# STM32Ethernet.net
KiCad netlist of a schematic drawn in Altium Designer
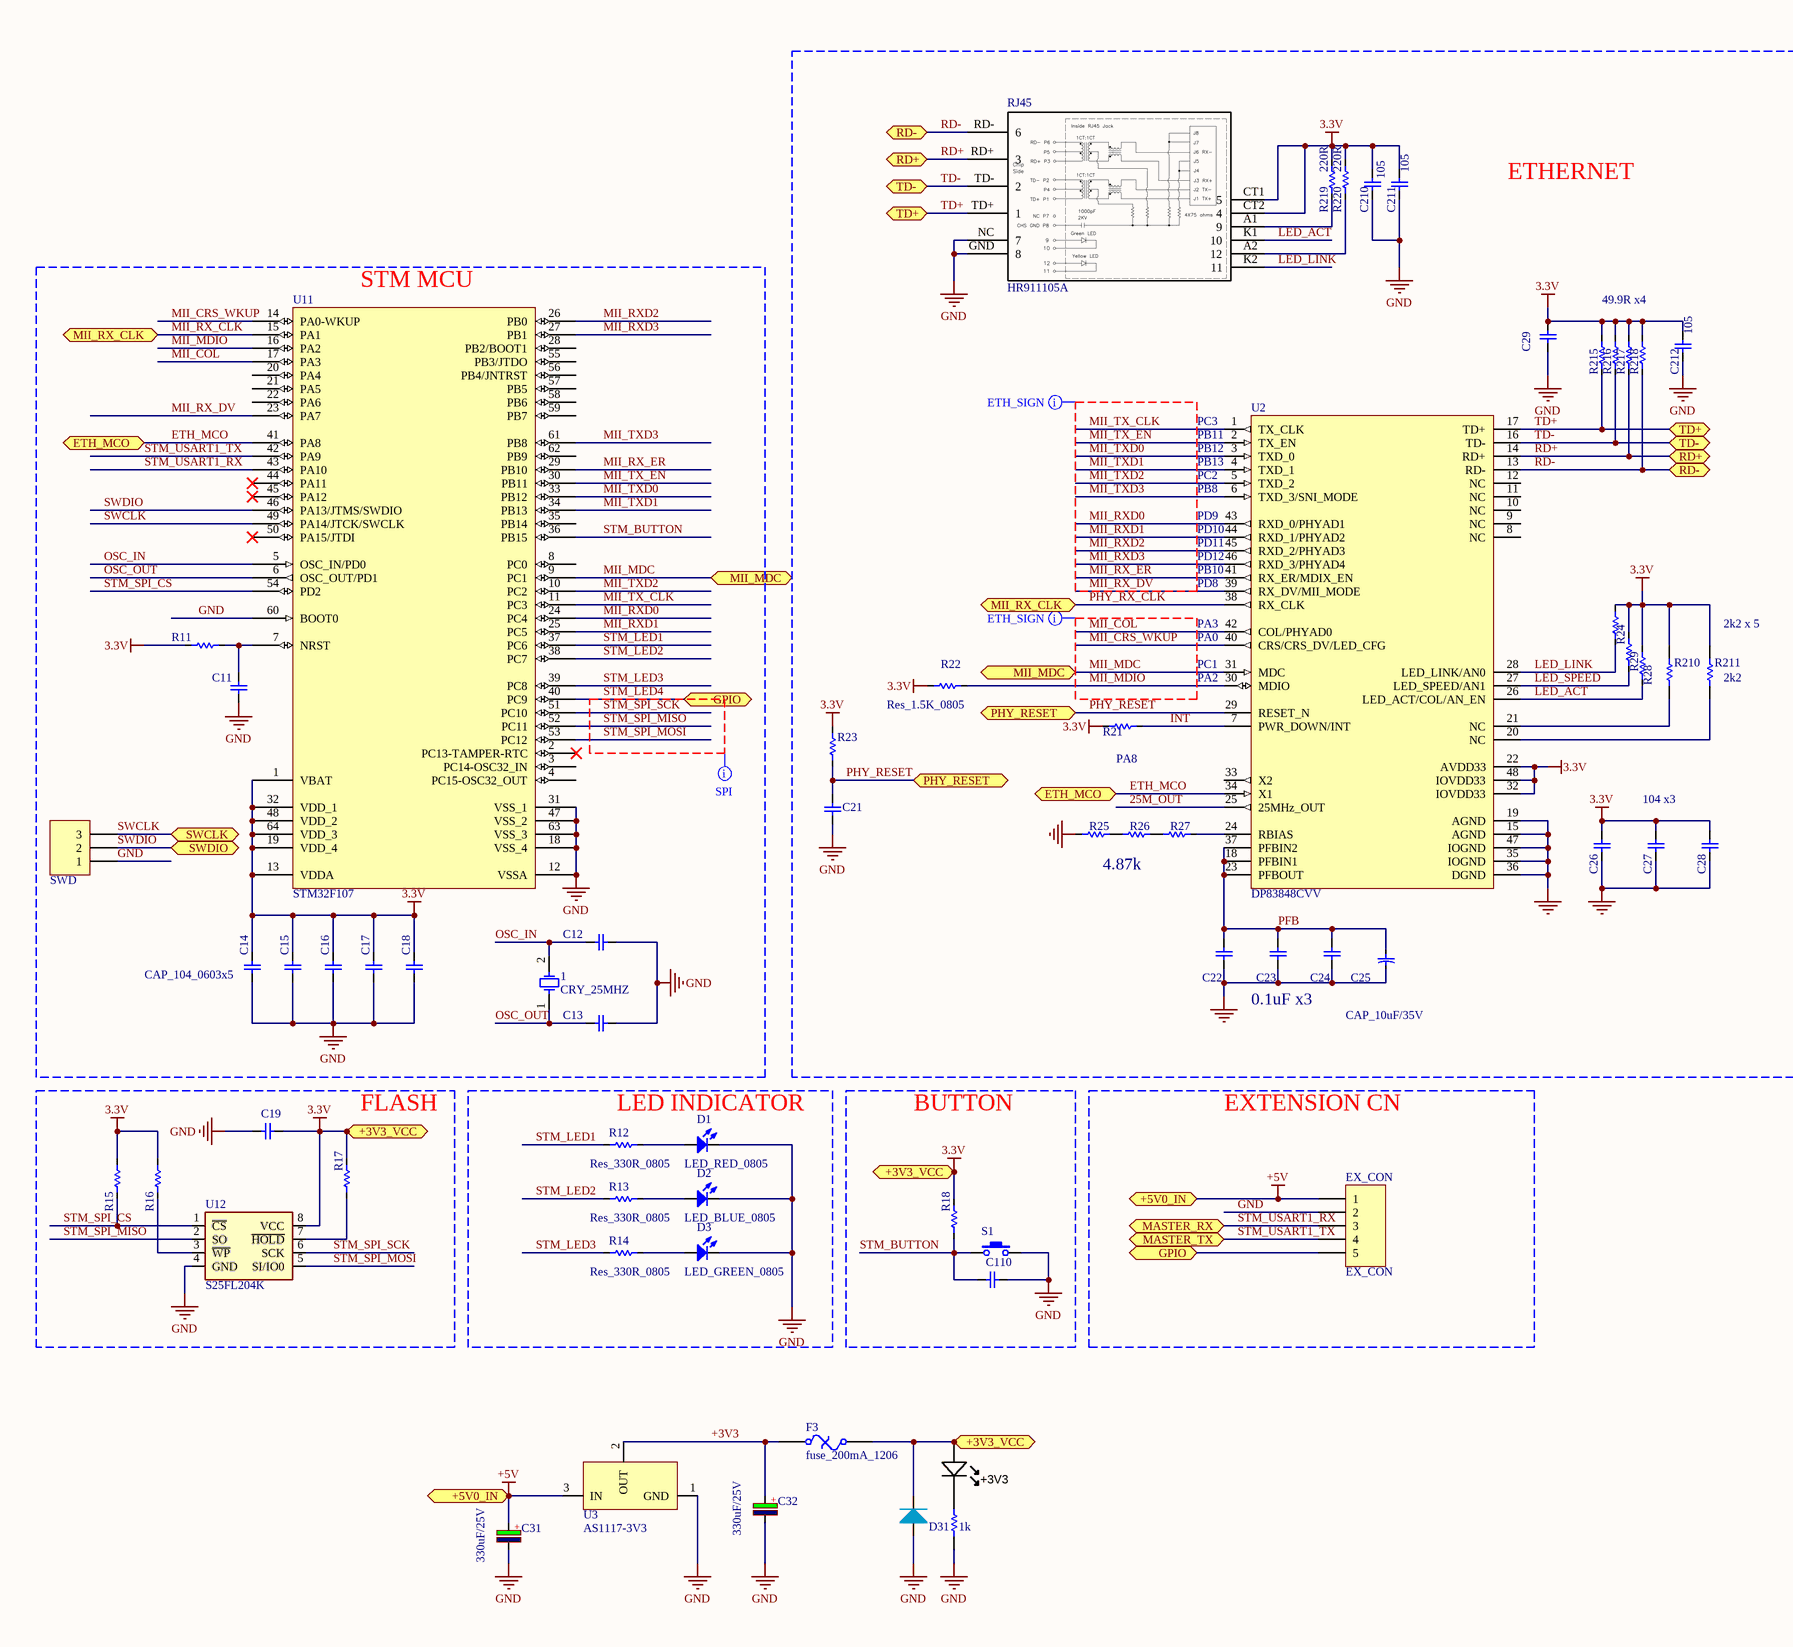
[diagram p0: STM32Ethernet.SchDoc, left]
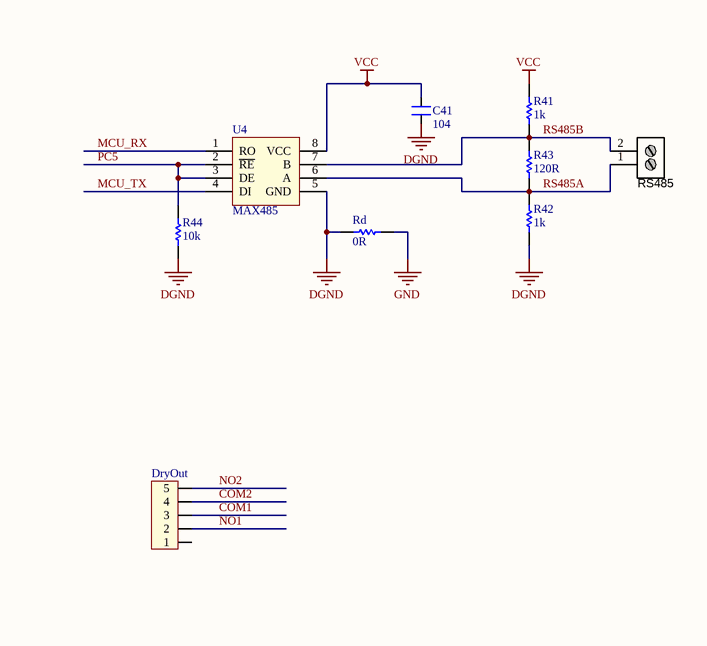
[diagram p1: STM32Ethernet.SchDoc, right]

(export (version "E")
  (design (tool "Eeschema 10.0.6"))
  (components
    (comp (ref "+3V3")
      (value "Blue")
      (footprint "LED-0805-K")
      (description "LED 0805 SMD Blue 100mcd 470nm")
      (libsource (lib "PBL - Light Sources") (part "LED_SMD_Blue_0805_100mcd"))
    )
    (comp (ref "1")
      (value "CRY_25MHZ")
      (footprint "cry")
      (description "Crystal Oscillator")
      (fields (field (name "PUBLISHER") "Altium Limited"))
      (libsource (lib "THU VIEN CHAN") (part "cry"))
    )
    (comp (ref "C11")
      (value "CAP_102_0603")
      (footprint "CAP_0805_TOP")
      (description "Capacitor")
      (fields (field (name "PUBLISHER") "Altium Limited"))
      (libsource (lib "THU VIEN CHAN") (part "Cap 1206 BUT"))
    )
    (comp (ref "C12")
      (value "CAP_18pF_0603")
      (footprint "CAP_0603_TOP")
      (description "Capacitor")
      (fields (field (name "PUBLISHER") "Altium Limited"))
      (libsource (lib "THU VIEN CHAN") (part "Cap 1206 BUT"))
    )
    (comp (ref "C13")
      (value "CAP_18pF_0603")
      (footprint "CAP_0603_TOP")
      (description "Capacitor")
      (fields (field (name "PUBLISHER") "Altium Limited"))
      (libsource (lib "THU VIEN CHAN") (part "Cap 1206 BUT"))
    )
    (comp (ref "C14")
      (value "CAP_104_0603")
      (footprint "CAPC1608N_F")
      (description "Capacitor")
      (fields (field (name "PUBLISHER") "Altium Limited"))
      (libsource (lib "THU VIEN CHAN") (part "Cap 1206 BUT"))
    )
    (comp (ref "C15")
      (value "CAP_104_0603")
      (footprint "CAPC1608N_F")
      (description "Capacitor")
      (fields (field (name "PUBLISHER") "Altium Limited"))
      (libsource (lib "THU VIEN CHAN") (part "Cap 1206 BUT"))
    )
    (comp (ref "C16")
      (value "CAP_104_0603")
      (footprint "CAPC1608N_F")
      (description "Capacitor")
      (fields (field (name "PUBLISHER") "Altium Limited"))
      (libsource (lib "THU VIEN CHAN") (part "Cap 1206 BUT"))
    )
    (comp (ref "C17")
      (value "CAP_104_0603")
      (footprint "CAPC1608N_F")
      (description "Capacitor")
      (fields (field (name "PUBLISHER") "Altium Limited"))
      (libsource (lib "THU VIEN CHAN") (part "Cap 1206 BUT"))
    )
    (comp (ref "C18")
      (value "CAP_104_0603")
      (footprint "CAPC1608N_F")
      (description "Capacitor")
      (fields (field (name "PUBLISHER") "Altium Limited"))
      (libsource (lib "THU VIEN CHAN") (part "Cap 1206 BUT"))
    )
    (comp (ref "C19")
      (value "CAP_104_0603")
      (footprint "CAP_0805_TOP")
      (description "Capacitor")
      (fields (field (name "PUBLISHER") "Altium Limited"))
      (libsource (lib "THU VIEN CHAN") (part "Cap 1206 BUT"))
    )
    (comp (ref "C21")
      (value "CAP_102_0603")
      (footprint "CAPC1608N_F")
      (description "Capacitor")
      (fields (field (name "PUBLISHER") "Altium Limited"))
      (libsource (lib "THU VIEN CHAN") (part "Cap 1206 BUT"))
    )
    (comp (ref "C22")
      (value "CAP_104_0603")
      (footprint "CAPC1608N_F")
      (description "Capacitor")
      (fields (field (name "PUBLISHER") "Altium Limited"))
      (libsource (lib "THU VIEN CHAN") (part "Cap 1206 BUT"))
    )
    (comp (ref "C23")
      (value "CAP_104_0603")
      (footprint "CAPC1608N_F")
      (description "Capacitor")
      (fields (field (name "PUBLISHER") "Altium Limited"))
      (libsource (lib "THU VIEN CHAN") (part "Cap 1206 BUT"))
    )
    (comp (ref "C24")
      (value "CAP_104_0603")
      (footprint "CAPC1608N_F")
      (description "Capacitor")
      (fields (field (name "PUBLISHER") "Altium Limited"))
      (libsource (lib "THU VIEN CHAN") (part "Cap 1206 BUT"))
    )
    (comp (ref "C25")
      (value "CAP_10uF/35V")
      (footprint "CAP_10uF/35V")
      (fields (field (name "PUBLISHER") "Altium Limited"))
      (libsource (lib "THU VIEN CHAN") (part "CAP P"))
    )
    (comp (ref "C26")
      (value "CAP_104_0603")
      (footprint "CAPC1608N_F")
      (description "Capacitor")
      (fields (field (name "PUBLISHER") "Altium Limited"))
      (libsource (lib "THU VIEN CHAN") (part "Cap 1206 BUT"))
    )
    (comp (ref "C27")
      (value "CAP_104_0603")
      (footprint "CAPC1608N_F")
      (description "Capacitor")
      (fields (field (name "PUBLISHER") "Altium Limited"))
      (libsource (lib "THU VIEN CHAN") (part "Cap 1206 BUT"))
    )
    (comp (ref "C28")
      (value "CAP_104_0603")
      (footprint "CAPC1608N_F")
      (description "Capacitor")
      (fields (field (name "PUBLISHER") "Altium Limited"))
      (libsource (lib "THU VIEN CHAN") (part "Cap 1206 BUT"))
    )
    (comp (ref "C29")
      (value "CAP_104_0603")
      (footprint "CAPC2012N_F")
      (description "Capacitor")
      (fields (field (name "PUBLISHER") "Altium Limited"))
      (libsource (lib "THU VIEN CHAN") (part "Cap 1206 BUT"))
    )
    (comp (ref "C31")
      (value "330uF/25V")
      (footprint "PBL - SMD Packages:CAPMP3528X210N")
      (description "Cap 1000uF/16V - 220uF/50V")
      (libsource (lib "heromap") (part "CP4"))
    )
    (comp (ref "C32")
      (value "330uF/25V")
      (footprint "CAPMP3528X210N")
      (description "Cap 1000uF/16V - 220uF/50V")
      (libsource (lib "heromap") (part "CP4"))
    )
    (comp (ref "C41")
      (value "104")
      (footprint "CAPC2012N_F")
      (fields (field (name "Comment") "100nF/104"))
      (libsource (lib "Tuan") (part "CAP NP"))
    )
    (comp (ref "C110")
      (value "CAP_102_0603")
      (footprint "CAP_0805_TOP")
      (description "Capacitor")
      (fields (field (name "PUBLISHER") "Altium Limited"))
      (libsource (lib "THU VIEN CHAN") (part "Cap 1206 BUT"))
    )
    (comp (ref "C210")
      (value "105")
      (footprint "CAPC1608N_F")
      (description "Capacitor")
      (fields (field (name "PUBLISHER") "Altium Limited"))
      (libsource (lib "THU VIEN CHAN") (part "Cap 1206 BUT"))
    )
    (comp (ref "C211")
      (value "105")
      (footprint "CAPC1608N_F")
      (description "Capacitor")
      (fields (field (name "PUBLISHER") "Altium Limited"))
      (libsource (lib "THU VIEN CHAN") (part "Cap 1206 BUT"))
    )
    (comp (ref "C212")
      (value "105")
      (footprint "CAPC2012N_F")
      (description "Capacitor")
      (fields (field (name "PUBLISHER") "Altium Limited"))
      (libsource (lib "THU VIEN CHAN") (part "Cap 1206 BUT"))
    )
    (comp (ref "D1")
      (value "LED_RED_0805")
      (footprint "LED 0805 TOP")
      (description "Typical INFRARED GaAs LED")
      (fields (field (name "PUBLISHER") "Altium Limited"))
      (libsource (lib "THU VIEN CHAN v1") (part "LED 0805 TOP"))
    )
    (comp (ref "D2")
      (value "LED_BLUE_0805")
      (footprint "LED 0805 TOP")
      (description "Typical INFRARED GaAs LED")
      (fields (field (name "PUBLISHER") "Altium Limited"))
      (libsource (lib "THU VIEN CHAN v1") (part "LED 0805 TOP"))
    )
    (comp (ref "D3")
      (value "LED_GREEN_0805")
      (footprint "LED 0805 TOP")
      (description "Typical INFRARED GaAs LED")
      (fields (field (name "PUBLISHER") "Altium Limited"))
      (libsource (lib "THU VIEN CHAN v1") (part "LED 0805 TOP"))
    )
    (comp (ref "D31") (value "Diode") (footprint "DO-214AC") (libsource (lib "Tuan") (part "Diode")))
    (comp (ref "DryOut")
      (value "JP5")
      (footprint "heromap:CON5")
      (description "Connector 5")
      (libsource (lib "heromap") (part "Con5"))
    )
    (comp (ref "EX_CON")
      (value "EX_CON")
      (footprint "HDR1X5")
      (description "Header, 5-Pin")
      (fields (field (name "PUBLISHER") "Altium Limited"))
      (libsource (lib "Miscellaneous Connectors") (part "Header 5"))
    )
    (comp (ref "F3")
      (value "fuse_200mA_1206")
      (footprint "SMD 1206")
      (description "Thermal Fuse")
      (fields (field (name "PUBLISHER") "Altium Limited"))
      (libsource (lib "Miscellaneous Devices") (part "Fuse Thermal"))
    )
    (comp (ref "R11")
      (value "Res_4.7K_0805")
      (footprint "RES_0805_TOP")
      (description "Resistor")
      (fields (field (name "PUBLISHER") "Altium Limited"))
      (libsource (lib "THU VIEN CHAN") (part "Res"))
    )
    (comp (ref "R12")
      (value "Res_330R_0805")
      (footprint "RES_0805_TOP")
      (description "Resistor")
      (fields (field (name "PUBLISHER") "Altium Limited"))
      (libsource (lib "THU VIEN CHAN") (part "Res"))
    )
    (comp (ref "R13")
      (value "Res_330R_0805")
      (footprint "RES_0805_TOP")
      (description "Resistor")
      (fields (field (name "PUBLISHER") "Altium Limited"))
      (libsource (lib "THU VIEN CHAN") (part "Res"))
    )
    (comp (ref "R14")
      (value "Res_330R_0805")
      (footprint "RES_0805_TOP")
      (description "Resistor")
      (fields (field (name "PUBLISHER") "Altium Limited"))
      (libsource (lib "THU VIEN CHAN") (part "Res"))
    )
    (comp (ref "R15")
      (value "Res_4.7K_0805")
      (footprint "RES_0805_TOP")
      (description "Resistor")
      (fields (field (name "PUBLISHER") "Altium Limited"))
      (libsource (lib "THU VIEN CHAN") (part "Res"))
    )
    (comp (ref "R16")
      (value "Res_4.7K_0805")
      (footprint "RES_0805_TOP")
      (description "Resistor")
      (fields (field (name "PUBLISHER") "Altium Limited"))
      (libsource (lib "THU VIEN CHAN") (part "Res"))
    )
    (comp (ref "R17")
      (value "Res_4.7K_0805")
      (footprint "RES_0805_TOP")
      (description "Resistor")
      (fields (field (name "PUBLISHER") "Altium Limited"))
      (libsource (lib "THU VIEN CHAN") (part "Res"))
    )
    (comp (ref "R18")
      (value "Res_4.7K_0805")
      (footprint "RES_0805_TOP")
      (description "Resistor")
      (fields (field (name "PUBLISHER") "Altium Limited"))
      (libsource (lib "THU VIEN CHAN") (part "Res"))
    )
    (comp (ref "R21")
      (value "Res_2.2K_0805")
      (footprint "RESC1608N_F")
      (description "Resistor")
      (fields (field (name "PUBLISHER") "Altium Limited"))
      (libsource (lib "THU VIEN CHAN") (part "Res"))
    )
    (comp (ref "R22")
      (value "Res_1.5K_0805")
      (footprint "RESC1608N_F")
      (description "Resistor")
      (fields (field (name "PUBLISHER") "Altium Limited"))
      (libsource (lib "") (part "Res_1"))
    )
    (comp (ref "R23")
      (value "Res_4.7K_0805")
      (footprint "RESC1608N_F")
      (description "Resistor")
      (fields (field (name "PUBLISHER") "Altium Limited"))
      (libsource (lib "") (part "Res_1"))
    )
    (comp (ref "R24")
      (value "Res_2.2K_0805")
      (footprint "RESC1608N_F")
      (description "Resistor")
      (fields (field (name "PUBLISHER") "Altium Limited"))
      (libsource (lib "THU VIEN CHAN") (part "Res"))
    )
    (comp (ref "R25")
      (value "Res_47R_0805")
      (footprint "RES_0805_TOP")
      (description "Resistor")
      (fields (field (name "PUBLISHER") "Altium Limited"))
      (libsource (lib "THU VIEN CHAN") (part "Res"))
    )
    (comp (ref "R26")
      (value "Res_120R_0805")
      (footprint "RES_0805_TOP")
      (description "Resistor")
      (fields (field (name "PUBLISHER") "Altium Limited"))
      (libsource (lib "THU VIEN CHAN") (part "Res"))
    )
    (comp (ref "R27")
      (value "Res_4.7K_0805")
      (footprint "RES_0805_TOP")
      (description "Resistor")
      (fields (field (name "PUBLISHER") "Altium Limited"))
      (libsource (lib "THU VIEN CHAN") (part "Res"))
    )
    (comp (ref "R28")
      (value "Res_0R_0603")
      (footprint "RESC1608N_F")
      (description "Resistor")
      (fields (field (name "PUBLISHER") "Altium Limited"))
      (libsource (lib "THU VIEN CHAN") (part "Res"))
    )
    (comp (ref "R29")
      (value "Res_0R_0603")
      (footprint "RESC1608N_F")
      (description "Resistor")
      (fields (field (name "PUBLISHER") "Altium Limited"))
      (libsource (lib "THU VIEN CHAN") (part "Res"))
    )
    (comp (ref "R41")
      (value "1k")
      (footprint "RESC2012N_F")
      (description "Tro dan")
      (libsource (lib "GPS_Clock_v12") (part "Res"))
    )
    (comp (ref "R42")
      (value "1k")
      (footprint "RESC2012N_F")
      (description "Tro dan")
      (libsource (lib "GPS_Clock_v12") (part "Res"))
    )
    (comp (ref "R43")
      (value "120R")
      (footprint "RESC2012N_F")
      (description "Tro dan")
      (fields (field (name "Comment") "330R"))
      (libsource (lib "GPS_Clock_v12") (part "Res"))
    )
    (comp (ref "R44")
      (value "10k")
      (footprint "RESC2012N_F")
      (description "Tro dan")
      (fields (field (name "Comment") "330R"))
      (libsource (lib "GPS_Clock_v12") (part "Res"))
    )
    (comp (ref "R210") (value "2k2") (footprint "RESC1608N_F") (libsource (lib "Tuan") (part "Res")))
    (comp (ref "R211") (value "2k2") (footprint "RESC1608N_F") (libsource (lib "Tuan") (part "Res")))
    (comp (ref "R215")
      (value "Res_49.9R_0805")
      (footprint "RES_0805_TOP")
      (description "Resistor")
      (fields (field (name "PUBLISHER") "Altium Limited"))
      (libsource (lib "THU VIEN CHAN") (part "Res"))
    )
    (comp (ref "R216")
      (value "Res_49.9R_0805")
      (footprint "RES_0805_TOP")
      (description "Resistor")
      (fields (field (name "PUBLISHER") "Altium Limited"))
      (libsource (lib "THU VIEN CHAN") (part "Res"))
    )
    (comp (ref "R217")
      (value "Res_49.9R_0805")
      (footprint "RES_0805_TOP")
      (description "Resistor")
      (fields (field (name "PUBLISHER") "Altium Limited"))
      (libsource (lib "THU VIEN CHAN") (part "Res"))
    )
    (comp (ref "R218")
      (value "Res_49.9R_0805")
      (footprint "RES_0805_TOP")
      (description "Resistor")
      (fields (field (name "PUBLISHER") "Altium Limited"))
      (libsource (lib "THU VIEN CHAN") (part "Res"))
    )
    (comp (ref "R219")
      (value "220R")
      (footprint "RESC1608N_F")
      (description "Resistor")
      (fields (field (name "PUBLISHER") "Altium Limited"))
      (libsource (lib "THU VIEN CHAN") (part "Res"))
    )
    (comp (ref "R220")
      (value "220R")
      (footprint "RESC1608N_F")
      (description "Resistor")
      (fields (field (name "PUBLISHER") "Altium Limited"))
      (libsource (lib "THU VIEN CHAN") (part "Res"))
    )
    (comp (ref "Rd")
      (value "0R")
      (footprint "RESC2012N_F")
      (fields (field (name "Comment") "Res"))
      (libsource (lib "Tuan") (part "Res"))
    )
    (comp (ref "RJ45") (value "HR911105A") (footprint "HR911105A") (libsource (lib "Tuan") (part "RJ45-LED")))
    (comp (ref "Rled")
      (value "1k")
      (footprint "RESC2012N_F")
      (fields (field (name "Comment") "Res_0805_1k"))
      (libsource (lib "Tuan") (part "Res"))
    )
    (comp (ref "RS485")
      (value "Stackable ScrewTerm")
      (footprint "2P_PCB1")
      (description "Terminal Block Screw Type THT 2-Position 3.81mm pitch")
      (libsource (lib "PBL - Connectors") (part "2P_ScrewTerm_90S_3.81MM"))
    )
    (comp (ref "S1")
      (value "BUTTON 2P")
      (footprint "Nut nhan 2 chan  dung")
      (description "Switch")
      (fields (field (name "PUBLISHER") "Altium Limited"))
      (libsource (lib "THU VIEN CHAN v1") (part "BUTTON 2P"))
    )
    (comp (ref "SWD")
      (value "Header 3")
      (footprint "heromap:HDR1X3")
      (description "Header, 3-Pin")
      (fields (field (name "PUBLISHER") "Altium Limited"))
      (libsource (lib "heromap") (part "Header 3"))
    )
    (comp (ref "U2")
      (value "DP83848CVV")
      (footprint "LQFP48")
      (libsource (lib "THU VIEN CHAN v1") (part "DP83848CVV"))
    )
    (comp (ref "U3") (value "AS1117-3V3") (footprint "SOT223-4N") (libsource (lib "Tuan") (part "AS1117")))
    (comp (ref "U4")
      (value "MAX485")
      (footprint "SO-8")
      (description "RS232 - RS485 (Same sn75176)")
      (libsource (lib "heromap") (part "MAX485"))
    )
    (comp (ref "U11")
      (value "STM32F107")
      (footprint "LQFP64_N")
      (description "STM32 ARM-based 32-bit MCU with 128 Kbytes Flash, 64-pin LQFP, Industrial Temperature")
      (fields (field (name "PUBLISHER") "Altium Limited"))
      (libsource (lib "ST Microcontroller 32-Bit STM32") (part "STM32F103RBT6"))
    )
    (comp (ref "U12")
      (value "S25FL204K")
      (footprint "SOIC_8")
      (libsource (lib "THU VIEN CHAN v1") (part "S25FL204K"))
    )
  )
  (nets
    (net (code "1") (name "+5V") (class "Default")
      (node (ref "C31") (pin "1") (pinfunction "1_1") (pintype "passive"))
      (node (ref "EX_CON") (pin "1") (pinfunction "1_1") (pintype "passive"))
      (node (ref "U3") (pin "3") (pinfunction "IN_3") (pintype "power_in"))
    )
    (net (code "2") (name "/+3V3") (class "Default")
      (node (ref "C32") (pin "1") (pinfunction "1_1") (pintype "passive"))
      (node (ref "F3") (pin "1") (pinfunction "1_1") (pintype "passive"))
      (node (ref "U3") (pin "2") (pinfunction "OUT_2") (pintype "power_in"))
    )
    (net (code "3") (name "/25M_OUT") (class "Default")
      (node (ref "U2") (pin "25") (pinfunction "25MHz_OUT_25") (pintype "output"))
    )
    (net (code "4") (name "/COM1") (class "Default")
      (node (ref "DryOut") (pin "3") (pinfunction "3_3") (pintype "passive"))
    )
    (net (code "5") (name "/COM2") (class "Default")
      (node (ref "DryOut") (pin "4") (pinfunction "4_4") (pintype "passive"))
    )
    (net (code "6") (name "/ETH_MCO") (class "Default")
      (node (ref "U11") (pin "41") (pinfunction "PA8_41") (pintype "bidirectional"))
      (node (ref "U2") (pin "34") (pinfunction "X1_34") (pintype "input"))
    )
    (net (code "7") (name "/INT") (class "Default")
      (node (ref "R21") (pin "1") (pinfunction "1_1") (pintype "passive"))
      (node (ref "U2") (pin "7") (pinfunction "PWR_DOWN/INT_7") (pintype "passive"))
    )
    (net (code "8") (name "/LED_ACT") (class "Default")
      (node (ref "R28") (pin "2") (pinfunction "2_2") (pintype "passive"))
      (node (ref "RJ45") (pin "K1") (pinfunction "10_K1") (pintype "passive"))
      (node (ref "U2") (pin "26") (pinfunction "LED_ACT/COL/AN_EN_26") (pintype "passive"))
    )
    (net (code "9") (name "/LED_LINK") (class "Default")
      (node (ref "R24") (pin "1") (pinfunction "1_1") (pintype "passive"))
      (node (ref "RJ45") (pin "K2") (pinfunction "11_K2") (pintype "passive"))
      (node (ref "U2") (pin "28") (pinfunction "LED_LINK/AN0_28") (pintype "passive"))
    )
    (net (code "10") (name "/LED_SPEED") (class "Default")
      (node (ref "R29") (pin "1") (pinfunction "1_1") (pintype "passive"))
      (node (ref "U2") (pin "27") (pinfunction "LED_SPEED/AN1_27") (pintype "passive"))
    )
    (net (code "11") (name "/MCU_RX") (class "Default")
      (node (ref "U4") (pin "1") (pinfunction "RO_1") (pintype "passive"))
    )
    (net (code "12") (name "/MCU_TX") (class "Default")
      (node (ref "U4") (pin "4") (pinfunction "DI_4") (pintype "passive"))
    )
    (net (code "13") (name "/MII_COL") (class "Default")
      (node (ref "U11") (pin "17") (pinfunction "PA3_17") (pintype "bidirectional"))
      (node (ref "U2") (pin "42") (pinfunction "COL/PHYAD0_42") (pintype "output"))
    )
    (net (code "14") (name "/MII_CRS_WKUP") (class "Default")
      (node (ref "U11") (pin "14") (pinfunction "PA0-WKUP_14") (pintype "bidirectional"))
      (node (ref "U2") (pin "40") (pinfunction "CRS/CRS_DV/LED_CFG_40") (pintype "output"))
    )
    (net (code "15") (name "/MII_MDC") (class "Default")
      (node (ref "U11") (pin "9") (pinfunction "PC1_9") (pintype "bidirectional"))
      (node (ref "U2") (pin "31") (pinfunction "MDC_31") (pintype "input"))
    )
    (net (code "16") (name "/MII_MDIO") (class "Default")
      (node (ref "R22") (pin "2") (pinfunction "2_2") (pintype "passive"))
      (node (ref "U11") (pin "16") (pinfunction "PA2_16") (pintype "bidirectional"))
      (node (ref "U2") (pin "30") (pinfunction "MDIO_30") (pintype "bidirectional"))
    )
    (net (code "17") (name "/MII_RXD0") (class "Default")
      (node (ref "U11") (pin "24") (pinfunction "PC4_24") (pintype "bidirectional"))
      (node (ref "U2") (pin "43") (pinfunction "RXD_0/PHYAD1_43") (pintype "output"))
    )
    (net (code "18") (name "/MII_RXD1") (class "Default")
      (node (ref "U11") (pin "25") (pinfunction "PC5_25") (pintype "bidirectional"))
      (node (ref "U2") (pin "44") (pinfunction "RXD_1/PHYAD2_44") (pintype "output"))
    )
    (net (code "19") (name "/MII_RXD2") (class "Default")
      (node (ref "U11") (pin "26") (pinfunction "PB0_26") (pintype "bidirectional"))
      (node (ref "U2") (pin "45") (pinfunction "RXD_2/PHYAD3_45") (pintype "output"))
    )
    (net (code "20") (name "/MII_RXD3") (class "Default")
      (node (ref "U11") (pin "27") (pinfunction "PB1_27") (pintype "bidirectional"))
      (node (ref "U2") (pin "46") (pinfunction "RXD_3/PHYAD4_46") (pintype "output"))
    )
    (net (code "21") (name "/MII_RX_CLK") (class "Default")
      (node (ref "U11") (pin "15") (pinfunction "PA1_15") (pintype "bidirectional"))
      (node (ref "U2") (pin "38") (pinfunction "RX_CLK_38") (pintype "output"))
    )
    (net (code "22") (name "/MII_RX_DV") (class "Default")
      (node (ref "U11") (pin "23") (pinfunction "PA7_23") (pintype "bidirectional"))
      (node (ref "U2") (pin "39") (pinfunction "RX_DV/MII_MODE_39") (pintype "output"))
    )
    (net (code "23") (name "/MII_RX_ER") (class "Default")
      (node (ref "U11") (pin "29") (pinfunction "PB10_29") (pintype "bidirectional"))
      (node (ref "U2") (pin "41") (pinfunction "RX_ER/MDIX_EN_41") (pintype "output"))
    )
    (net (code "24") (name "/MII_TXD0") (class "Default")
      (node (ref "U11") (pin "33") (pinfunction "PB12_33") (pintype "bidirectional"))
      (node (ref "U2") (pin "3") (pinfunction "TXD_0_3") (pintype "input"))
    )
    (net (code "25") (name "/MII_TXD1") (class "Default")
      (node (ref "U11") (pin "34") (pinfunction "PB13_34") (pintype "bidirectional"))
      (node (ref "U2") (pin "4") (pinfunction "TXD_1_4") (pintype "input"))
    )
    (net (code "26") (name "/MII_TXD2") (class "Default")
      (node (ref "U11") (pin "10") (pinfunction "PC2_10") (pintype "bidirectional"))
      (node (ref "U2") (pin "5") (pinfunction "TXD_2_5") (pintype "input"))
    )
    (net (code "27") (name "/MII_TXD3") (class "Default")
      (node (ref "U11") (pin "61") (pinfunction "PB8_61") (pintype "bidirectional"))
      (node (ref "U2") (pin "6") (pinfunction "TXD_3/SNI_MODE_6") (pintype "input"))
    )
    (net (code "28") (name "/MII_TX_CLK") (class "Default")
      (node (ref "U11") (pin "11") (pinfunction "PC3_11") (pintype "bidirectional"))
      (node (ref "U2") (pin "1") (pinfunction "TX_CLK_1") (pintype "output"))
    )
    (net (code "29") (name "/MII_TX_EN") (class "Default")
      (node (ref "U11") (pin "30") (pinfunction "PB11_30") (pintype "bidirectional"))
      (node (ref "U2") (pin "2") (pinfunction "TX_EN_2") (pintype "input"))
    )
    (net (code "30") (name "/NO1") (class "Default")
      (node (ref "DryOut") (pin "2") (pinfunction "2_2") (pintype "passive"))
    )
    (net (code "31") (name "/NO2") (class "Default")
      (node (ref "DryOut") (pin "5") (pinfunction "5_5") (pintype "passive"))
    )
    (net (code "32") (name "/OSC_IN") (class "Default")
      (node (ref "1") (pin "2") (pinfunction "OSC2_2") (pintype "passive"))
      (node (ref "C12") (pin "1") (pinfunction "1_1") (pintype "passive"))
      (node (ref "U11") (pin "5") (pinfunction "OSC_IN/PD0_5") (pintype "input"))
    )
    (net (code "33") (name "/OSC_OUT") (class "Default")
      (node (ref "1") (pin "1") (pinfunction "OSC1_1") (pintype "passive"))
      (node (ref "C13") (pin "1") (pinfunction "1_1") (pintype "passive"))
      (node (ref "U11") (pin "6") (pinfunction "OSC_OUT/PD1_6") (pintype "output"))
    )
    (net (code "34") (name "/PC5") (class "Default")
      (node (ref "R44") (pin "2") (pinfunction "2_2") (pintype "passive"))
      (node (ref "U4") (pin "2") (pinfunction "~{RE}_2") (pintype "passive"))
      (node (ref "U4") (pin "3") (pinfunction "DE_3") (pintype "passive"))
    )
    (net (code "35") (name "/PFB") (class "Default")
      (node (ref "C22") (pin "2") (pinfunction "2_2") (pintype "passive"))
      (node (ref "C23") (pin "2") (pinfunction "2_2") (pintype "passive"))
      (node (ref "C24") (pin "2") (pinfunction "2_2") (pintype "passive"))
      (node (ref "C25") (pin "1") (pinfunction "1_1") (pintype "passive"))
      (node (ref "U2") (pin "18") (pinfunction "PFBIN1_18") (pintype "passive"))
      (node (ref "U2") (pin "23") (pinfunction "PFBOUT_23") (pintype "passive"))
      (node (ref "U2") (pin "37") (pinfunction "PFBIN2_37") (pintype "passive"))
    )
    (net (code "36") (name "/PHY_RESET") (class "Default")
      (node (ref "C21") (pin "2") (pinfunction "2_2") (pintype "passive"))
      (node (ref "R23") (pin "1") (pinfunction "1_1") (pintype "passive"))
      (node (ref "U2") (pin "29") (pinfunction "RESET_N_29") (pintype "passive"))
    )
    (net (code "37") (name "/RD+") (class "Default")
      (node (ref "R217") (pin "2") (pinfunction "2_2") (pintype "passive"))
      (node (ref "RJ45") (pin "RD+") (pinfunction "3_RD+") (pintype "passive"))
      (node (ref "U2") (pin "14") (pinfunction "RD+_14") (pintype "passive"))
    )
    (net (code "38") (name "/RD-") (class "Default")
      (node (ref "R218") (pin "2") (pinfunction "2_2") (pintype "passive"))
      (node (ref "RJ45") (pin "RD-") (pinfunction "6_RD-") (pintype "passive"))
      (node (ref "U2") (pin "13") (pinfunction "RD-_13") (pintype "passive"))
    )
    (net (code "39") (name "/RS485A") (class "Default")
      (node (ref "R42") (pin "2") (pinfunction "2_2") (pintype "passive"))
      (node (ref "R43") (pin "1") (pinfunction "1_1") (pintype "passive"))
      (node (ref "RS485") (pin "1") (pinfunction "1_1") (pintype "passive"))
      (node (ref "U4") (pin "6") (pinfunction "A_6") (pintype "passive"))
    )
    (net (code "40") (name "/RS485B") (class "Default")
      (node (ref "R41") (pin "1") (pinfunction "1_1") (pintype "passive"))
      (node (ref "R43") (pin "2") (pinfunction "2_2") (pintype "passive"))
      (node (ref "RS485") (pin "2") (pinfunction "2_2") (pintype "passive"))
      (node (ref "U4") (pin "7") (pinfunction "B_7") (pintype "passive"))
    )
    (net (code "41") (name "/STM_BUTTON") (class "Default")
      (node (ref "C110") (pin "1") (pinfunction "1_1") (pintype "passive"))
      (node (ref "R18") (pin "2") (pinfunction "2_2") (pintype "passive"))
      (node (ref "S1") (pin "1") (pinfunction "1_1") (pintype "passive"))
      (node (ref "U11") (pin "36") (pinfunction "PB15_36") (pintype "bidirectional"))
    )
    (net (code "42") (name "/STM_LED1") (class "Default")
      (node (ref "R12") (pin "1") (pinfunction "1_1") (pintype "passive"))
      (node (ref "U11") (pin "37") (pinfunction "PC6_37") (pintype "bidirectional"))
    )
    (net (code "43") (name "/STM_LED2") (class "Default")
      (node (ref "R13") (pin "1") (pinfunction "1_1") (pintype "passive"))
      (node (ref "U11") (pin "38") (pinfunction "PC7_38") (pintype "bidirectional"))
    )
    (net (code "44") (name "/STM_LED3") (class "Default")
      (node (ref "R14") (pin "1") (pinfunction "1_1") (pintype "passive"))
      (node (ref "U11") (pin "39") (pinfunction "PC8_39") (pintype "bidirectional"))
    )
    (net (code "45") (name "/STM_LED4") (class "Default")
      (node (ref "EX_CON") (pin "5") (pinfunction "5_5") (pintype "passive"))
      (node (ref "U11") (pin "40") (pinfunction "PC9_40") (pintype "bidirectional"))
    )
    (net (code "46") (name "/STM_SPI_CS") (class "Default")
      (node (ref "R15") (pin "2") (pinfunction "2_2") (pintype "passive"))
      (node (ref "U11") (pin "54") (pinfunction "PD2_54") (pintype "bidirectional"))
      (node (ref "U12") (pin "1") (pinfunction "~{CS}_1") (pintype "passive"))
    )
    (net (code "47") (name "/STM_SPI_MISO") (class "Default")
      (node (ref "U11") (pin "52") (pinfunction "PC11_52") (pintype "bidirectional"))
      (node (ref "U12") (pin "2") (pinfunction "SO_2") (pintype "passive"))
    )
    (net (code "48") (name "/STM_SPI_MOSI") (class "Default")
      (node (ref "U11") (pin "53") (pinfunction "PC12_53") (pintype "bidirectional"))
      (node (ref "U12") (pin "5") (pinfunction "SI/IO0_5") (pintype "passive"))
    )
    (net (code "49") (name "/STM_SPI_SCK") (class "Default")
      (node (ref "U11") (pin "51") (pinfunction "PC10_51") (pintype "bidirectional"))
      (node (ref "U12") (pin "6") (pinfunction "SCK_6") (pintype "passive"))
    )
    (net (code "50") (name "/STM_USART1_RX") (class "Default")
      (node (ref "EX_CON") (pin "3") (pinfunction "3_3") (pintype "passive"))
      (node (ref "U11") (pin "43") (pinfunction "PA10_43") (pintype "bidirectional"))
    )
    (net (code "51") (name "/STM_USART1_TX") (class "Default")
      (node (ref "EX_CON") (pin "4") (pinfunction "4_4") (pintype "passive"))
      (node (ref "U11") (pin "42") (pinfunction "PA9_42") (pintype "bidirectional"))
    )
    (net (code "52") (name "/SWCLK") (class "Default")
      (node (ref "SWD") (pin "3") (pinfunction "3_3") (pintype "passive"))
      (node (ref "U11") (pin "49") (pinfunction "PA14/JTCK/SWCLK_49") (pintype "bidirectional"))
    )
    (net (code "53") (name "/SWDIO") (class "Default")
      (node (ref "SWD") (pin "2") (pinfunction "2_2") (pintype "passive"))
      (node (ref "U11") (pin "46") (pinfunction "PA13/JTMS/SWDIO_46") (pintype "bidirectional"))
    )
    (net (code "54") (name "/TD+") (class "Default")
      (node (ref "R215") (pin "2") (pinfunction "2_2") (pintype "passive"))
      (node (ref "RJ45") (pin "TD+") (pinfunction "1_TD+") (pintype "passive"))
      (node (ref "U2") (pin "17") (pinfunction "TD+_17") (pintype "passive"))
    )
    (net (code "55") (name "/TD-") (class "Default")
      (node (ref "R216") (pin "2") (pinfunction "2_2") (pintype "passive"))
      (node (ref "RJ45") (pin "TD-") (pinfunction "2_TD-") (pintype "passive"))
      (node (ref "U2") (pin "16") (pinfunction "TD-_16") (pintype "passive"))
    )
    (net (code "56") (name "3.3V") (class "Default")
      (node (ref "+3V3") (pin "A") (pinfunction "A_A") (pintype "passive"))
      (node (ref "C14") (pin "1") (pinfunction "1_1") (pintype "passive"))
      (node (ref "C15") (pin "1") (pinfunction "1_1") (pintype "passive"))
      (node (ref "C16") (pin "1") (pinfunction "1_1") (pintype "passive"))
      (node (ref "C17") (pin "1") (pinfunction "1_1") (pintype "passive"))
      (node (ref "C18") (pin "1") (pinfunction "1_1") (pintype "passive"))
      (node (ref "C19") (pin "1") (pinfunction "1_1") (pintype "passive"))
      (node (ref "C210") (pin "1") (pinfunction "1_1") (pintype "passive"))
      (node (ref "C211") (pin "1") (pinfunction "1_1") (pintype "passive"))
      (node (ref "C212") (pin "1") (pinfunction "1_1") (pintype "passive"))
      (node (ref "C26") (pin "2") (pinfunction "2_2") (pintype "passive"))
      (node (ref "C27") (pin "1") (pinfunction "1_1") (pintype "passive"))
      (node (ref "C28") (pin "2") (pinfunction "2_2") (pintype "passive"))
      (node (ref "C29") (pin "1") (pinfunction "1_1") (pintype "passive"))
      (node (ref "D31") (pin "2") (pinfunction "K_2") (pintype "passive"))
      (node (ref "F3") (pin "2") (pinfunction "2_2") (pintype "passive"))
      (node (ref "R11") (pin "2") (pinfunction "2_2") (pintype "passive"))
      (node (ref "R15") (pin "1") (pinfunction "1_1") (pintype "passive"))
      (node (ref "R16") (pin "1") (pinfunction "1_1") (pintype "passive"))
      (node (ref "R17") (pin "1") (pinfunction "1_1") (pintype "passive"))
      (node (ref "R18") (pin "1") (pinfunction "1_1") (pintype "passive"))
      (node (ref "R21") (pin "2") (pinfunction "2_2") (pintype "passive"))
      (node (ref "R210") (pin "2") (pinfunction "2_2") (pintype "passive"))
      (node (ref "R211") (pin "2") (pinfunction "2_2") (pintype "passive"))
      (node (ref "R215") (pin "1") (pinfunction "1_1") (pintype "passive"))
      (node (ref "R216") (pin "1") (pinfunction "1_1") (pintype "passive"))
      (node (ref "R217") (pin "1") (pinfunction "1_1") (pintype "passive"))
      (node (ref "R218") (pin "1") (pinfunction "1_1") (pintype "passive"))
      (node (ref "R219") (pin "1") (pinfunction "1_1") (pintype "passive"))
      (node (ref "R22") (pin "1") (pinfunction "1_1") (pintype "passive"))
      (node (ref "R220") (pin "1") (pinfunction "1_1") (pintype "passive"))
      (node (ref "R23") (pin "2") (pinfunction "2_2") (pintype "passive"))
      (node (ref "R24") (pin "2") (pinfunction "2_2") (pintype "passive"))
      (node (ref "R28") (pin "1") (pinfunction "1_1") (pintype "passive"))
      (node (ref "R29") (pin "2") (pinfunction "2_2") (pintype "passive"))
      (node (ref "RJ45") (pin "CT1") (pinfunction "5_CT1") (pintype "passive"))
      (node (ref "RJ45") (pin "CT2") (pinfunction "4_CT2") (pintype "passive"))
      (node (ref "U11") (pin "1") (pinfunction "VBAT_1") (pintype "power_in"))
      (node (ref "U11") (pin "13") (pinfunction "VDDA_13") (pintype "power_in"))
      (node (ref "U11") (pin "19") (pinfunction "VDD_4_19") (pintype "power_in"))
      (node (ref "U11") (pin "32") (pinfunction "VDD_1_32") (pintype "power_in"))
      (node (ref "U11") (pin "48") (pinfunction "VDD_2_48") (pintype "power_in"))
      (node (ref "U11") (pin "64") (pinfunction "VDD_3_64") (pintype "power_in"))
      (node (ref "U12") (pin "8") (pinfunction "VCC_8") (pintype "passive"))
      (node (ref "U2") (pin "22") (pinfunction "AVDD33_22") (pintype "passive"))
      (node (ref "U2") (pin "32") (pinfunction "IOVDD33_32") (pintype "passive"))
      (node (ref "U2") (pin "48") (pinfunction "IOVDD33_48") (pintype "passive"))
    )
    (net (code "57") (name "DGND") (class "Default")
      (node (ref "C41") (pin "1") (pinfunction "1_1") (pintype "passive"))
      (node (ref "R42") (pin "1") (pinfunction "1_1") (pintype "passive"))
      (node (ref "R44") (pin "1") (pinfunction "1_1") (pintype "passive"))
      (node (ref "Rd") (pin "1") (pinfunction "1_1") (pintype "passive"))
      (node (ref "U4") (pin "5") (pinfunction "GND_5") (pintype "passive"))
    )
    (net (code "58") (name "GND") (class "Default")
      (node (ref "C11") (pin "2") (pinfunction "2_2") (pintype "passive"))
      (node (ref "C110") (pin "2") (pinfunction "2_2") (pintype "passive"))
      (node (ref "C12") (pin "2") (pinfunction "2_2") (pintype "passive"))
      (node (ref "C13") (pin "2") (pinfunction "2_2") (pintype "passive"))
      (node (ref "C14") (pin "2") (pinfunction "2_2") (pintype "passive"))
      (node (ref "C15") (pin "2") (pinfunction "2_2") (pintype "passive"))
      (node (ref "C16") (pin "2") (pinfunction "2_2") (pintype "passive"))
      (node (ref "C17") (pin "2") (pinfunction "2_2") (pintype "passive"))
      (node (ref "C18") (pin "2") (pinfunction "2_2") (pintype "passive"))
      (node (ref "C19") (pin "2") (pinfunction "2_2") (pintype "passive"))
      (node (ref "C21") (pin "1") (pinfunction "1_1") (pintype "passive"))
      (node (ref "C210") (pin "2") (pinfunction "2_2") (pintype "passive"))
      (node (ref "C211") (pin "2") (pinfunction "2_2") (pintype "passive"))
      (node (ref "C212") (pin "2") (pinfunction "2_2") (pintype "passive"))
      (node (ref "C22") (pin "1") (pinfunction "1_1") (pintype "passive"))
      (node (ref "C23") (pin "1") (pinfunction "1_1") (pintype "passive"))
      (node (ref "C24") (pin "1") (pinfunction "1_1") (pintype "passive"))
      (node (ref "C25") (pin "2") (pinfunction "2_2") (pintype "passive"))
      (node (ref "C26") (pin "1") (pinfunction "1_1") (pintype "passive"))
      (node (ref "C27") (pin "2") (pinfunction "2_2") (pintype "passive"))
      (node (ref "C28") (pin "1") (pinfunction "1_1") (pintype "passive"))
      (node (ref "C29") (pin "2") (pinfunction "2_2") (pintype "passive"))
      (node (ref "C31") (pin "2") (pinfunction "2_2") (pintype "passive"))
      (node (ref "C32") (pin "2") (pinfunction "2_2") (pintype "passive"))
      (node (ref "D1") (pin "2") (pinfunction "K_2") (pintype "passive"))
      (node (ref "D2") (pin "2") (pinfunction "K_2") (pintype "passive"))
      (node (ref "D3") (pin "2") (pinfunction "K_2") (pintype "passive"))
      (node (ref "D31") (pin "1") (pinfunction "A_1") (pintype "passive"))
      (node (ref "EX_CON") (pin "2") (pinfunction "2_2") (pintype "passive"))
      (node (ref "R25") (pin "2") (pinfunction "2_2") (pintype "passive"))
      (node (ref "RJ45") (pin "GND") (pinfunction "8_GND") (pintype "passive"))
      (node (ref "RJ45") (pin "NC") (pinfunction "7_NC") (pintype "passive"))
      (node (ref "Rd") (pin "2") (pinfunction "2_2") (pintype "passive"))
      (node (ref "Rled") (pin "2") (pinfunction "2_2") (pintype "passive"))
      (node (ref "S1") (pin "2") (pinfunction "2_2") (pintype "passive"))
      (node (ref "SWD") (pin "1") (pinfunction "1_1") (pintype "passive"))
      (node (ref "U11") (pin "12") (pinfunction "VSSA_12") (pintype "power_in"))
      (node (ref "U11") (pin "18") (pinfunction "VSS_4_18") (pintype "power_in"))
      (node (ref "U11") (pin "31") (pinfunction "VSS_1_31") (pintype "power_in"))
      (node (ref "U11") (pin "47") (pinfunction "VSS_2_47") (pintype "power_in"))
      (node (ref "U11") (pin "60") (pinfunction "BOOT0_60") (pintype "input"))
      (node (ref "U11") (pin "63") (pinfunction "VSS_3_63") (pintype "power_in"))
      (node (ref "U12") (pin "4") (pinfunction "GND_4") (pintype "passive"))
      (node (ref "U2") (pin "15") (pinfunction "AGND_15") (pintype "passive"))
      (node (ref "U2") (pin "19") (pinfunction "AGND_19") (pintype "passive"))
      (node (ref "U2") (pin "35") (pinfunction "IOGND_35") (pintype "passive"))
      (node (ref "U2") (pin "36") (pinfunction "DGND_36") (pintype "passive"))
      (node (ref "U2") (pin "47") (pinfunction "IOGND_47") (pintype "passive"))
      (node (ref "U3") (pin "1") (pinfunction "GND_1") (pintype "power_in"))
    )
    (net (code "59") (name "Net-(+3V3-PadK)") (class "Default")
      (node (ref "+3V3") (pin "K") (pinfunction "K_K") (pintype "passive"))
      (node (ref "Rled") (pin "1") (pinfunction "1_1") (pintype "passive"))
    )
    (net (code "60") (name "Net-(D1-A)") (class "Default")
      (node (ref "D1") (pin "1") (pinfunction "A_1") (pintype "passive"))
      (node (ref "R12") (pin "2") (pinfunction "2_2") (pintype "passive"))
    )
    (net (code "61") (name "Net-(D2-A)") (class "Default")
      (node (ref "D2") (pin "1") (pinfunction "A_1") (pintype "passive"))
      (node (ref "R13") (pin "2") (pinfunction "2_2") (pintype "passive"))
    )
    (net (code "62") (name "Net-(D3-A)") (class "Default")
      (node (ref "D3") (pin "1") (pinfunction "A_1") (pintype "passive"))
      (node (ref "R14") (pin "2") (pinfunction "2_2") (pintype "passive"))
    )
    (net (code "63") (name "Net-(R25-Pad1)") (class "Default")
      (node (ref "R25") (pin "1") (pinfunction "1_1") (pintype "passive"))
      (node (ref "R26") (pin "1") (pinfunction "1_1") (pintype "passive"))
    )
    (net (code "64") (name "Net-(R26-Pad2)") (class "Default")
      (node (ref "R26") (pin "2") (pinfunction "2_2") (pintype "passive"))
      (node (ref "R27") (pin "2") (pinfunction "2_2") (pintype "passive"))
    )
    (net (code "65") (name "Net-(R210-Pad1)") (class "Default")
      (node (ref "R210") (pin "1") (pinfunction "1_1") (pintype "passive"))
      (node (ref "U2") (pin "21") (pinfunction "NC_21") (pintype "passive"))
    )
    (net (code "66") (name "Net-(R211-Pad1)") (class "Default")
      (node (ref "R211") (pin "1") (pinfunction "1_1") (pintype "passive"))
      (node (ref "U2") (pin "20") (pinfunction "NC_20") (pintype "passive"))
    )
    (net (code "67") (name "Net-(RJ45-9)") (class "Default")
      (node (ref "R219") (pin "2") (pinfunction "2_2") (pintype "passive"))
      (node (ref "RJ45") (pin "A1") (pinfunction "9_A1") (pintype "passive"))
    )
    (net (code "68") (name "Net-(RJ45-12)") (class "Default")
      (node (ref "R220") (pin "2") (pinfunction "2_2") (pintype "passive"))
      (node (ref "RJ45") (pin "A2") (pinfunction "12_A2") (pintype "passive"))
    )
    (net (code "69") (name "Net-(U2-RBIAS)") (class "Default")
      (node (ref "R27") (pin "1") (pinfunction "1_1") (pintype "passive"))
      (node (ref "U2") (pin "24") (pinfunction "RBIAS_24") (pintype "passive"))
    )
    (net (code "70") (name "Net-(U11-NRST)") (class "Default")
      (node (ref "C11") (pin "1") (pinfunction "1_1") (pintype "passive"))
      (node (ref "R11") (pin "1") (pinfunction "1_1") (pintype "passive"))
      (node (ref "U11") (pin "7") (pinfunction "NRST_7") (pintype "bidirectional"))
    )
    (net (code "71") (name "Net-(U12-~{HOLD})") (class "Default")
      (node (ref "R17") (pin "2") (pinfunction "2_2") (pintype "passive"))
      (node (ref "U12") (pin "7") (pinfunction "~{HOLD}_7") (pintype "passive"))
    )
    (net (code "72") (name "Net-(U12-~{WP})") (class "Default")
      (node (ref "R16") (pin "2") (pinfunction "2_2") (pintype "passive"))
      (node (ref "U12") (pin "3") (pinfunction "~{WP}_3") (pintype "passive"))
    )
    (net (code "73") (name "VCC") (class "Default")
      (node (ref "C41") (pin "2") (pinfunction "2_2") (pintype "passive"))
      (node (ref "R41") (pin "2") (pinfunction "2_2") (pintype "passive"))
      (node (ref "U4") (pin "8") (pinfunction "VCC_8") (pintype "passive"))
    )
    (net (code "74") (name "unconnected-(DryOut-Pad1)") (class "Default")
      (node (ref "DryOut") (pin "1") (pinfunction "1_1") (pintype "passive"))
    )
    (net (code "75") (name "unconnected-(U2-NC-Pad8)") (class "Default")
      (node (ref "U2") (pin "8") (pinfunction "NC_8") (pintype "passive"))
    )
    (net (code "76") (name "unconnected-(U2-NC-Pad9)") (class "Default")
      (node (ref "U2") (pin "9") (pinfunction "NC_9") (pintype "passive"))
    )
    (net (code "77") (name "unconnected-(U2-NC-Pad10)") (class "Default")
      (node (ref "U2") (pin "10") (pinfunction "NC_10") (pintype "passive"))
    )
    (net (code "78") (name "unconnected-(U2-NC-Pad11)") (class "Default")
      (node (ref "U2") (pin "11") (pinfunction "NC_11") (pintype "passive"))
    )
    (net (code "79") (name "unconnected-(U2-NC-Pad12)") (class "Default")
      (node (ref "U2") (pin "12") (pinfunction "NC_12") (pintype "passive"))
    )
    (net (code "80") (name "unconnected-(U2-X2-Pad33)") (class "Default")
      (node (ref "U2") (pin "33") (pinfunction "X2_33") (pintype "output"))
    )
    (net (code "81") (name "unconnected-(U11-PA4-Pad20)") (class "Default")
      (node (ref "U11") (pin "20") (pinfunction "PA4_20") (pintype "bidirectional"))
    )
    (net (code "82") (name "unconnected-(U11-PA5-Pad21)") (class "Default")
      (node (ref "U11") (pin "21") (pinfunction "PA5_21") (pintype "bidirectional"))
    )
    (net (code "83") (name "unconnected-(U11-PA6-Pad22)") (class "Default")
      (node (ref "U11") (pin "22") (pinfunction "PA6_22") (pintype "bidirectional"))
    )
    (net (code "84") (name "unconnected-(U11-PA11-Pad44)") (class "Default")
      (node (ref "U11") (pin "44") (pinfunction "PA11_44") (pintype "bidirectional+no_connect"))
    )
    (net (code "85") (name "unconnected-(U11-PA12-Pad45)") (class "Default")
      (node (ref "U11") (pin "45") (pinfunction "PA12_45") (pintype "bidirectional+no_connect"))
    )
    (net (code "86") (name "unconnected-(U11-PA15{slash}JTDI-Pad50)") (class "Default")
      (node (ref "U11") (pin "50") (pinfunction "PA15/JTDI_50") (pintype "bidirectional+no_connect"))
    )
    (net (code "87") (name "unconnected-(U11-PB2{slash}BOOT1-Pad28)") (class "Default")
      (node (ref "U11") (pin "28") (pinfunction "PB2/BOOT1_28") (pintype "bidirectional"))
    )
    (net (code "88") (name "unconnected-(U11-PB3{slash}JTDO-Pad55)") (class "Default")
      (node (ref "U11") (pin "55") (pinfunction "PB3/JTDO_55") (pintype "bidirectional"))
    )
    (net (code "89") (name "unconnected-(U11-PB4{slash}JNTRST-Pad56)") (class "Default")
      (node (ref "U11") (pin "56") (pinfunction "PB4/JNTRST_56") (pintype "bidirectional"))
    )
    (net (code "90") (name "unconnected-(U11-PB5-Pad57)") (class "Default")
      (node (ref "U11") (pin "57") (pinfunction "PB5_57") (pintype "bidirectional"))
    )
    (net (code "91") (name "unconnected-(U11-PB6-Pad58)") (class "Default")
      (node (ref "U11") (pin "58") (pinfunction "PB6_58") (pintype "bidirectional"))
    )
    (net (code "92") (name "unconnected-(U11-PB7-Pad59)") (class "Default")
      (node (ref "U11") (pin "59") (pinfunction "PB7_59") (pintype "bidirectional"))
    )
    (net (code "93") (name "unconnected-(U11-PB9-Pad62)") (class "Default")
      (node (ref "U11") (pin "62") (pinfunction "PB9_62") (pintype "bidirectional"))
    )
    (net (code "94") (name "unconnected-(U11-PB14-Pad35)") (class "Default")
      (node (ref "U11") (pin "35") (pinfunction "PB14_35") (pintype "bidirectional"))
    )
    (net (code "95") (name "unconnected-(U11-PC0-Pad8)") (class "Default")
      (node (ref "U11") (pin "8") (pinfunction "PC0_8") (pintype "bidirectional"))
    )
    (net (code "96") (name "unconnected-(U11-PC13-TAMPER-RTC-Pad2)") (class "Default")
      (node (ref "U11") (pin "2") (pinfunction "PC13-TAMPER-RTC_2") (pintype "bidirectional+no_connect"))
    )
    (net (code "97") (name "unconnected-(U11-PC14-OSC32_IN-Pad3)") (class "Default")
      (node (ref "U11") (pin "3") (pinfunction "PC14-OSC32_IN_3") (pintype "bidirectional"))
    )
    (net (code "98") (name "unconnected-(U11-PC15-OSC32_OUT-Pad4)") (class "Default")
      (node (ref "U11") (pin "4") (pinfunction "PC15-OSC32_OUT_4") (pintype "bidirectional"))
    )
  )
)
